# USBAdap.net
KiCad netlist of a schematic drawn in EAGLE
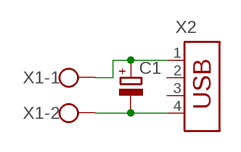
[diagram p0: schematic, sheet 1]

(export (version "E")
  (design (tool "Eeschema 10.0.6"))
  (components
    (comp (ref "C1")
      (value "CPOL-EUE5-8.5")
      (footprint "eagle-import:E5-8,5")
      (libsource (lib "eagle-import") (part "CPOL-EUE5-8.5"))
    )
    (comp (ref "X1")
      (value "W237-102")
      (footprint "eagle-import:W237-102")
      (fields (field (name "MPN") "237-102"))
      (libsource (lib "eagle-import") (part "W237-102"))
    )
    (comp (ref "X2")
      (value "USB-787616")
      (footprint "eagle-import:USB")
      (libsource (lib "eagle-import") (part "USB-787616"))
    )
  )
  (nets
    (net (code "1") (name "Net-(X1A-KL)") (class "Default")
      (node (ref "C1") (pin "+") (pinfunction "+_+") (pintype "passive"))
      (node (ref "X1") (pin "1") (pinfunction "KL_1") (pintype "passive"))
      (node (ref "X2") (pin "1") (pinfunction "1_1") (pintype "passive"))
    )
    (net (code "2") (name "Net-(X1B-KL)") (class "Default")
      (node (ref "C1") (pin "-") (pinfunction "-_-") (pintype "passive"))
      (node (ref "X1") (pin "2") (pinfunction "KL_2") (pintype "passive"))
      (node (ref "X2") (pin "4") (pinfunction "4_4") (pintype "passive"))
    )
    (net (code "3") (name "unconnected-(X2-Pad2)") (class "Default")
      (node (ref "X2") (pin "2") (pinfunction "2_2") (pintype "passive"))
    )
    (net (code "4") (name "unconnected-(X2-Pad3)") (class "Default")
      (node (ref "X2") (pin "3") (pinfunction "3_3") (pintype "passive"))
    )
  )
)
